# Load_Sig_Sch.net
KiCad netlist of a schematic drawn in EAGLE
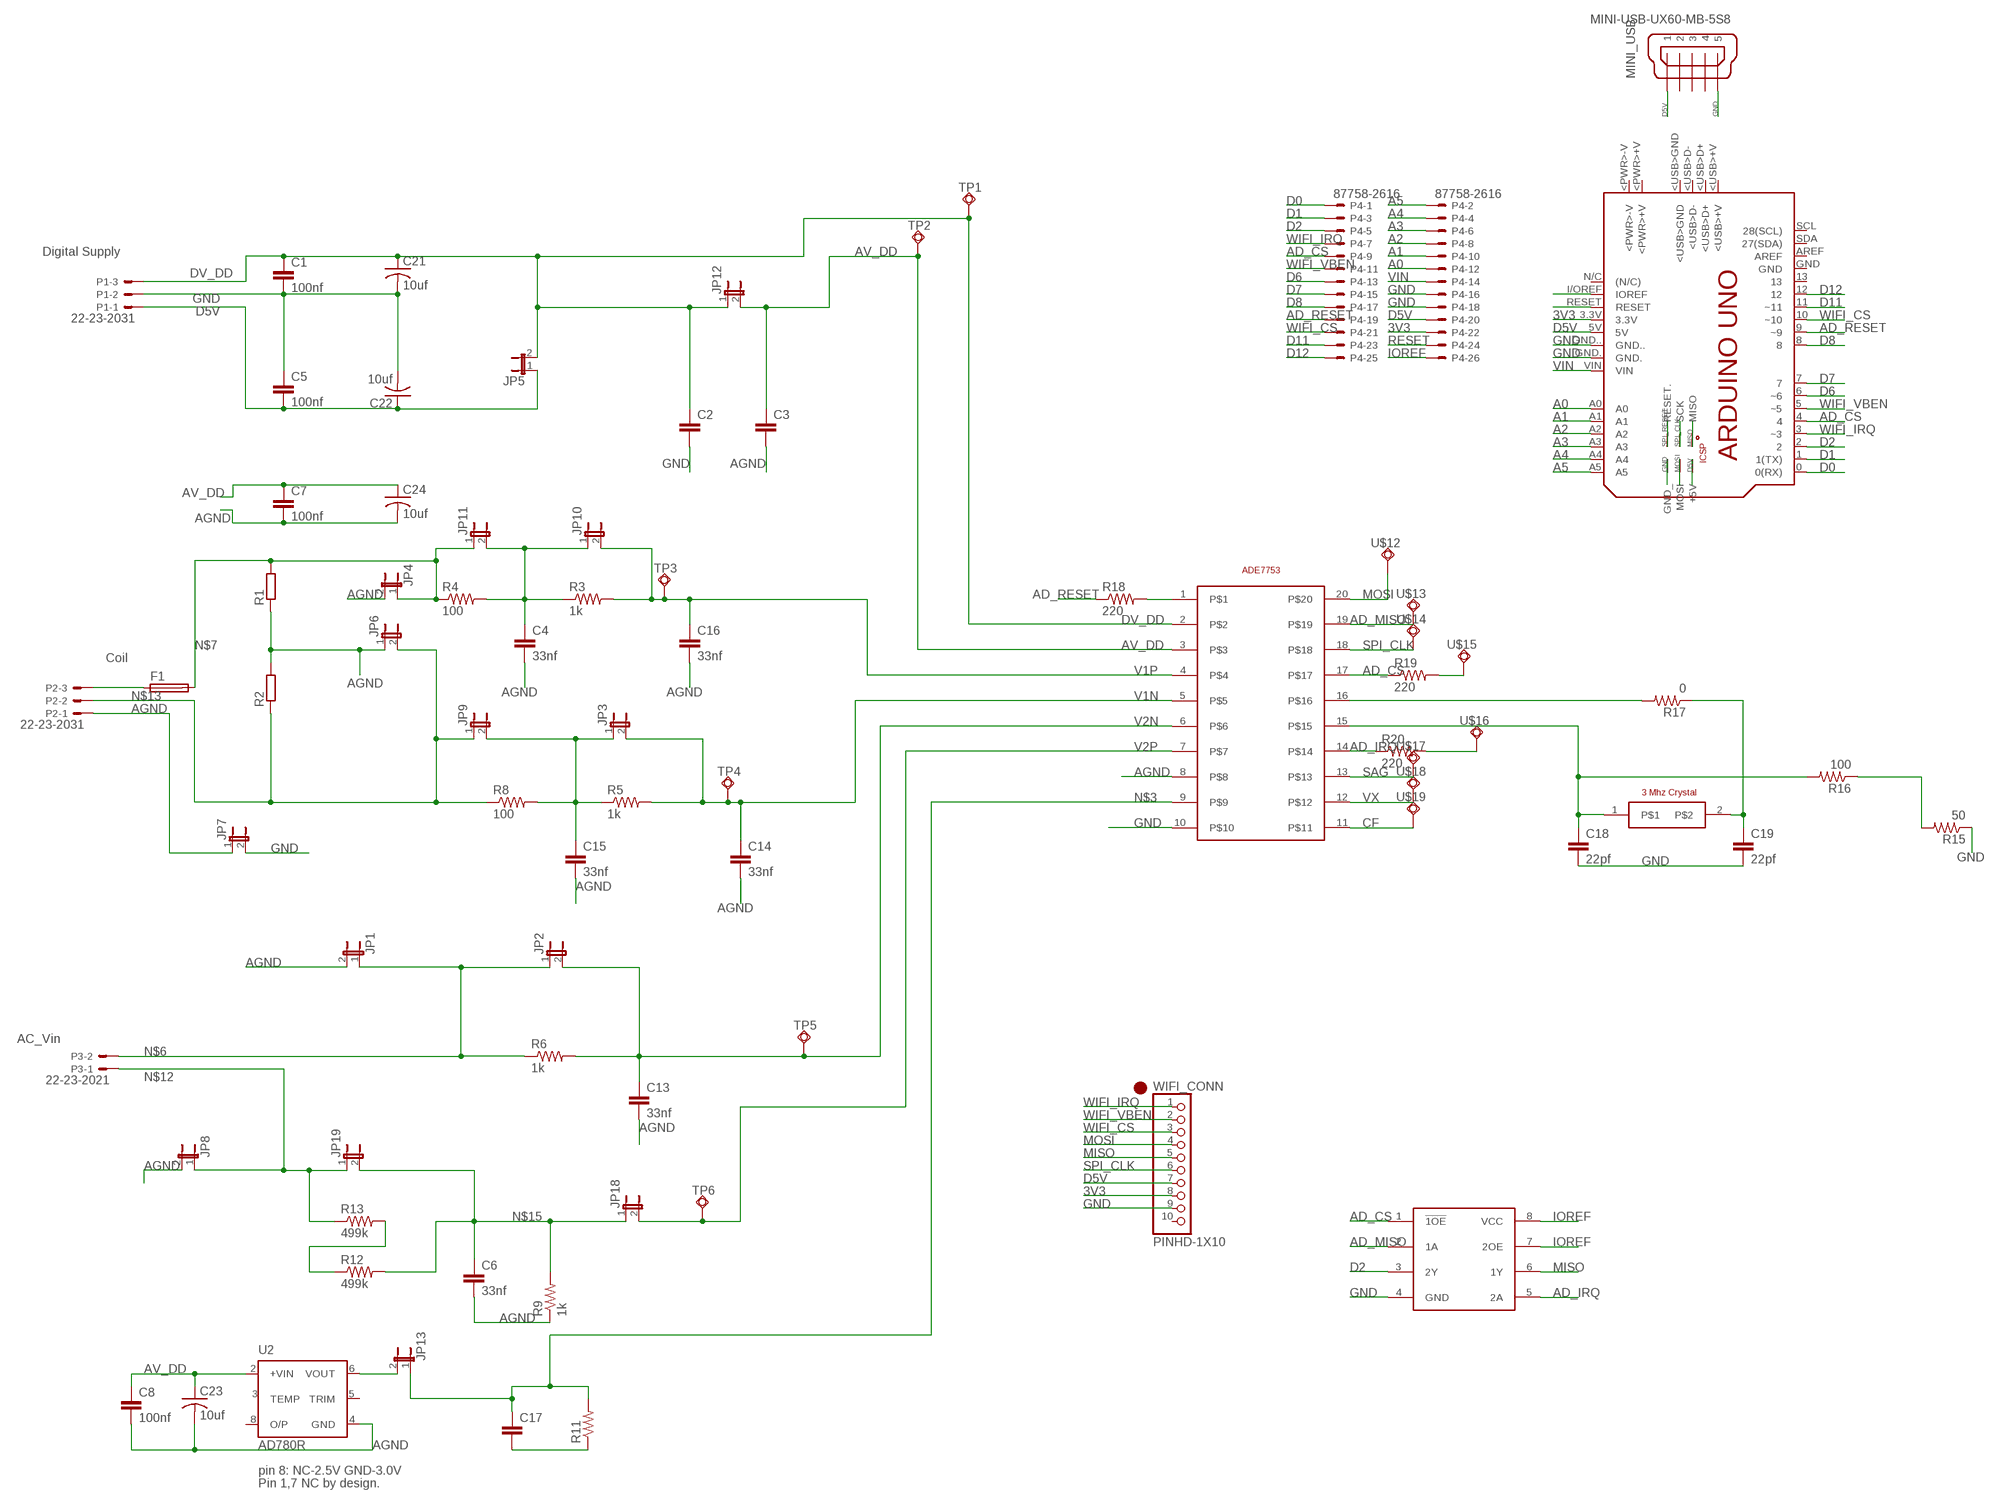
[diagram p0: schematic, sheet 1]

(export (version "E")
  (design (tool "Eeschema 10.0.6"))
  (components
    (comp (ref "C1")
      (value "100nf")
      (footprint "eagle-import:C025-024X044")
      (libsource (lib "eagle-import") (part "resistor_C-EU025-024X044"))
    )
    (comp (ref "C2")
      (value "C-EU025-024X044")
      (footprint "eagle-import:C025-024X044")
      (libsource (lib "eagle-import") (part "resistor_C-EU025-024X044"))
    )
    (comp (ref "C3")
      (value "C-EU025-024X044")
      (footprint "eagle-import:C025-024X044")
      (libsource (lib "eagle-import") (part "resistor_C-EU025-024X044"))
    )
    (comp (ref "C4")
      (value "33nf")
      (footprint "eagle-import:C025-024X044")
      (libsource (lib "eagle-import") (part "resistor_C-EU025-024X044"))
    )
    (comp (ref "C5")
      (value "100nf")
      (footprint "eagle-import:C025-024X044")
      (libsource (lib "eagle-import") (part "resistor_C-EU025-024X044"))
    )
    (comp (ref "C6")
      (value "33nf")
      (footprint "eagle-import:C025-024X044")
      (libsource (lib "eagle-import") (part "resistor_C-EU025-024X044"))
    )
    (comp (ref "C7")
      (value "100nf")
      (footprint "eagle-import:C025-024X044")
      (libsource (lib "eagle-import") (part "resistor_C-EU025-024X044"))
    )
    (comp (ref "C8")
      (value "100nf")
      (footprint "eagle-import:C025-024X044")
      (libsource (lib "eagle-import") (part "resistor_C-EU025-024X044"))
    )
    (comp (ref "C13")
      (value "33nf")
      (footprint "eagle-import:C025-024X044")
      (libsource (lib "eagle-import") (part "resistor_C-EU025-024X044"))
    )
    (comp (ref "C14")
      (value "33nf")
      (footprint "eagle-import:C025-024X044")
      (libsource (lib "eagle-import") (part "resistor_C-EU025-024X044"))
    )
    (comp (ref "C15")
      (value "33nf")
      (footprint "eagle-import:C025-024X044")
      (libsource (lib "eagle-import") (part "resistor_C-EU025-024X044"))
    )
    (comp (ref "C16")
      (value "33nf")
      (footprint "eagle-import:C025-024X044")
      (libsource (lib "eagle-import") (part "resistor_C-EU025-024X044"))
    )
    (comp (ref "C17")
      (value "C-EU025-024X044")
      (footprint "eagle-import:C025-024X044")
      (libsource (lib "eagle-import") (part "resistor_C-EU025-024X044"))
    )
    (comp (ref "C18")
      (value "22pf")
      (footprint "eagle-import:C025-024X044")
      (libsource (lib "eagle-import") (part "C-EU025-024X044"))
    )
    (comp (ref "C19")
      (value "22pf")
      (footprint "eagle-import:C025-024X044")
      (libsource (lib "eagle-import") (part "C-EU025-024X044"))
    )
    (comp (ref "C21")
      (value "10uf")
      (footprint "eagle-import:C025-024X044")
      (libsource (lib "eagle-import") (part "C-US025-024X044"))
    )
    (comp (ref "C22")
      (value "10uf")
      (footprint "eagle-import:C025-024X044")
      (libsource (lib "eagle-import") (part "C-US025-024X044"))
    )
    (comp (ref "C23")
      (value "10uf")
      (footprint "eagle-import:C025-024X044")
      (libsource (lib "eagle-import") (part "C-US025-024X044"))
    )
    (comp (ref "C24")
      (value "10uf")
      (footprint "eagle-import:C025-024X044")
      (libsource (lib "eagle-import") (part "C-US025-024X044"))
    )
    (comp (ref "F1")
      (value "19560")
      (footprint "eagle-import:19560")
      (fields (field (name "MPN") "56000001009"))
      (libsource (lib "eagle-import") (part "19560"))
    )
    (comp (ref "JP1")
      (value "JP1E")
      (footprint "eagle-import:JP1")
      (libsource (lib "eagle-import") (part "JP1E"))
    )
    (comp (ref "JP2")
      (value "JP1E")
      (footprint "eagle-import:JP1")
      (libsource (lib "eagle-import") (part "JP1E"))
    )
    (comp (ref "JP3")
      (value "JP1E")
      (footprint "eagle-import:JP1")
      (libsource (lib "eagle-import") (part "JP1E"))
    )
    (comp (ref "JP4")
      (value "JP1E")
      (footprint "eagle-import:JP1")
      (libsource (lib "eagle-import") (part "JP1E"))
    )
    (comp (ref "JP5")
      (value "JP1E")
      (footprint "eagle-import:JP1")
      (libsource (lib "eagle-import") (part "JP1E"))
    )
    (comp (ref "JP6")
      (value "JP1E")
      (footprint "eagle-import:JP1")
      (libsource (lib "eagle-import") (part "JP1E"))
    )
    (comp (ref "JP7")
      (value "JP1E")
      (footprint "eagle-import:JP1")
      (libsource (lib "eagle-import") (part "JP1E"))
    )
    (comp (ref "JP8")
      (value "JP1E")
      (footprint "eagle-import:JP1")
      (libsource (lib "eagle-import") (part "JP1E"))
    )
    (comp (ref "JP9")
      (value "JP1E")
      (footprint "eagle-import:JP1")
      (libsource (lib "eagle-import") (part "JP1E"))
    )
    (comp (ref "JP10")
      (value "JP1E")
      (footprint "eagle-import:JP1")
      (libsource (lib "eagle-import") (part "JP1E"))
    )
    (comp (ref "JP11")
      (value "JP1E")
      (footprint "eagle-import:JP1")
      (libsource (lib "eagle-import") (part "JP1E"))
    )
    (comp (ref "JP12")
      (value "JP1E")
      (footprint "eagle-import:JP1")
      (libsource (lib "eagle-import") (part "JP1E"))
    )
    (comp (ref "JP13")
      (value "JP1E")
      (footprint "eagle-import:JP1")
      (libsource (lib "eagle-import") (part "JP1E"))
    )
    (comp (ref "JP18")
      (value "JP1E")
      (footprint "eagle-import:JP1")
      (libsource (lib "eagle-import") (part "JP1E"))
    )
    (comp (ref "JP19")
      (value "JP1E")
      (footprint "eagle-import:JP1")
      (libsource (lib "eagle-import") (part "JP1E"))
    )
    (comp (ref "MINI_USB")
      (value "MINI-USB-UX60-MB-5S8")
      (footprint "eagle-import:UX60-MB-5S8")
      (libsource (lib "eagle-import") (part "MINI-USB-UX60-MB-5S8"))
    )
    (comp (ref "P1")
      (value "22-23-2031")
      (footprint "eagle-import:22-23-2031")
      (fields (field (name "MF") "MOLEX"))
      (libsource (lib "eagle-import") (part "22-23-2031"))
    )
    (comp (ref "P2")
      (value "22-23-2031")
      (footprint "eagle-import:22-23-2031")
      (fields (field (name "MF") "MOLEX"))
      (libsource (lib "eagle-import") (part "22-23-2031"))
    )
    (comp (ref "P3")
      (value "22-23-2021")
      (footprint "eagle-import:22-23-2021")
      (fields (field (name "MF") "MOLEX"))
      (libsource (lib "eagle-import") (part "22-23-2021"))
    )
    (comp (ref "P4")
      (value "87758-2616")
      (footprint "eagle-import:87758-2616")
      (libsource (lib "eagle-import") (part "87758-2616"))
    )
    (comp (ref "PCB1")
      (value "ARDUINO_UNO")
      (footprint "eagle-import:ARDUINO_UNO")
      (libsource (lib "eagle-import") (part "ARDUINO_UNO"))
    )
    (comp (ref "R1")
      (value "BVS")
      (footprint "eagle-import:BVS")
      (libsource (lib "eagle-import") (part "BVS"))
    )
    (comp (ref "R2")
      (value "BVS")
      (footprint "eagle-import:BVS")
      (libsource (lib "eagle-import") (part "BVS"))
    )
    (comp (ref "R3")
      (value "1k")
      (footprint "eagle-import:0204V")
      (libsource (lib "eagle-import") (part "R-US_0204/2V"))
    )
    (comp (ref "R4")
      (value "100")
      (footprint "eagle-import:0204V")
      (libsource (lib "eagle-import") (part "R-US_0204/2V"))
    )
    (comp (ref "R5")
      (value "1k")
      (footprint "eagle-import:0204V")
      (libsource (lib "eagle-import") (part "R-US_0204/2V"))
    )
    (comp (ref "R6")
      (value "1k")
      (footprint "eagle-import:0204V")
      (libsource (lib "eagle-import") (part "R-US_0204/2V"))
    )
    (comp (ref "R8")
      (value "100")
      (footprint "eagle-import:0204V")
      (libsource (lib "eagle-import") (part "R-US_0204/2V"))
    )
    (comp (ref "R9")
      (value "1k")
      (footprint "eagle-import:0204V")
      (libsource (lib "eagle-import") (part "R-US_0204/2V"))
    )
    (comp (ref "R11")
      (value "R-US_0204/2V")
      (footprint "eagle-import:0204V")
      (libsource (lib "eagle-import") (part "R-US_0204/2V"))
    )
    (comp (ref "R12")
      (value "499k")
      (footprint "eagle-import:0204V")
      (libsource (lib "eagle-import") (part "R-US_0204/2V"))
    )
    (comp (ref "R13")
      (value "499k")
      (footprint "eagle-import:0204V")
      (libsource (lib "eagle-import") (part "R-US_0204/2V"))
    )
    (comp (ref "R15")
      (value "50")
      (footprint "eagle-import:0204V")
      (libsource (lib "eagle-import") (part "R-US_0204/2V"))
    )
    (comp (ref "R16")
      (value "100")
      (footprint "eagle-import:0204V")
      (libsource (lib "eagle-import") (part "R-US_0204/2V"))
    )
    (comp (ref "R17")
      (value "0")
      (footprint "eagle-import:0204V")
      (libsource (lib "eagle-import") (part "R-US_0204/2V"))
    )
    (comp (ref "R18")
      (value "220")
      (footprint "eagle-import:0603-RES")
      (libsource (lib "eagle-import") (part "RESISTOR0603-RES"))
    )
    (comp (ref "R19")
      (value "220")
      (footprint "eagle-import:0603-RES")
      (libsource (lib "eagle-import") (part "RESISTOR0603-RES"))
    )
    (comp (ref "R20")
      (value "220")
      (footprint "eagle-import:0603-RES")
      (libsource (lib "eagle-import") (part "RESISTOR0603-RES"))
    )
    (comp (ref "TP1")
      (value "TEST")
      (footprint "eagle-import:TEST")
      (libsource (lib "eagle-import") (part "TEST"))
    )
    (comp (ref "TP2")
      (value "TEST")
      (footprint "eagle-import:TEST")
      (libsource (lib "eagle-import") (part "TEST"))
    )
    (comp (ref "TP3")
      (value "TEST")
      (footprint "eagle-import:TEST")
      (libsource (lib "eagle-import") (part "TEST"))
    )
    (comp (ref "TP4")
      (value "TEST")
      (footprint "eagle-import:TEST")
      (libsource (lib "eagle-import") (part "TEST"))
    )
    (comp (ref "TP5")
      (value "TEST")
      (footprint "eagle-import:TEST")
      (libsource (lib "eagle-import") (part "TEST"))
    )
    (comp (ref "TP6")
      (value "TEST")
      (footprint "eagle-import:TEST")
      (libsource (lib "eagle-import") (part "TEST"))
    )
    (comp (ref "U$2")
      (value "X079-ND_CRYSTAL")
      (footprint "eagle-import:HC49US")
      (libsource (lib "eagle-import") (part "X079-ND_CRYSTAL"))
    )
    (comp (ref "U$12")
      (value "TEST")
      (footprint "eagle-import:TEST")
      (libsource (lib "eagle-import") (part "TEST"))
    )
    (comp (ref "U$13")
      (value "TEST")
      (footprint "eagle-import:TEST")
      (libsource (lib "eagle-import") (part "TEST"))
    )
    (comp (ref "U$14")
      (value "TEST")
      (footprint "eagle-import:TEST")
      (libsource (lib "eagle-import") (part "TEST"))
    )
    (comp (ref "U$15")
      (value "TEST")
      (footprint "eagle-import:TEST")
      (libsource (lib "eagle-import") (part "TEST"))
    )
    (comp (ref "U$16")
      (value "TEST")
      (footprint "eagle-import:TEST")
      (libsource (lib "eagle-import") (part "TEST"))
    )
    (comp (ref "U$17")
      (value "TEST")
      (footprint "eagle-import:TEST")
      (libsource (lib "eagle-import") (part "TEST"))
    )
    (comp (ref "U$18")
      (value "TEST")
      (footprint "eagle-import:TEST")
      (libsource (lib "eagle-import") (part "TEST"))
    )
    (comp (ref "U$19")
      (value "TEST")
      (footprint "eagle-import:TEST")
      (libsource (lib "eagle-import") (part "TEST"))
    )
    (comp (ref "U1")
      (value "ADE7753")
      (footprint "eagle-import:SSOP20")
      (libsource (lib "eagle-import") (part "ADE7753"))
    )
    (comp (ref "U2")
      (value "AD780R")
      (footprint "eagle-import:SO8")
      (fields (field (name "MPN") "AD780BRZ-REEL"))
      (libsource (lib "eagle-import") (part "AD780R"))
    )
    (comp (ref "U3")
      (value "74LVC2G241")
      (footprint "eagle-import:SOP65P490X110-8N")
      (libsource (lib "eagle-import") (part "74LVC2G241"))
    )
    (comp (ref "WIFI_CONN")
      (value "PINHD-1X10")
      (footprint "eagle-import:1X10-BIG")
      (libsource (lib "eagle-import") (part "PINHD-1X10"))
    )
  )
  (nets
    (net (code "1") (name "/3V3") (class "Default")
      (node (ref "P4") (pin "22") (pinfunction "S_22") (pintype "passive"))
      (node (ref "PCB1") (pin "3.3V") (pinfunction "3.3V_3.3V") (pintype "bidirectional"))
      (node (ref "WIFI_CONN") (pin "8") (pinfunction "8_8") (pintype "passive"))
    )
    (net (code "2") (name "/A0") (class "Default")
      (node (ref "P4") (pin "12") (pinfunction "S_12") (pintype "passive"))
      (node (ref "PCB1") (pin "A0") (pinfunction "A0_A0") (pintype "bidirectional"))
    )
    (net (code "3") (name "/A1") (class "Default")
      (node (ref "P4") (pin "10") (pinfunction "S_10") (pintype "passive"))
      (node (ref "PCB1") (pin "A1") (pinfunction "A1_A1") (pintype "bidirectional"))
    )
    (net (code "4") (name "/A2") (class "Default")
      (node (ref "P4") (pin "8") (pinfunction "S_8") (pintype "passive"))
      (node (ref "PCB1") (pin "A2") (pinfunction "A2_A2") (pintype "bidirectional"))
    )
    (net (code "5") (name "/A3") (class "Default")
      (node (ref "P4") (pin "6") (pinfunction "S_6") (pintype "passive"))
      (node (ref "PCB1") (pin "A3") (pinfunction "A3_A3") (pintype "bidirectional"))
    )
    (net (code "6") (name "/A4") (class "Default")
      (node (ref "P4") (pin "4") (pinfunction "S_4") (pintype "passive"))
      (node (ref "PCB1") (pin "A4") (pinfunction "A4_A4") (pintype "bidirectional"))
    )
    (net (code "7") (name "/A5") (class "Default")
      (node (ref "P4") (pin "2") (pinfunction "S_2") (pintype "passive"))
      (node (ref "PCB1") (pin "A5") (pinfunction "A5_A5") (pintype "bidirectional"))
    )
    (net (code "8") (name "/AD_CS") (class "Default")
      (node (ref "P4") (pin "9") (pinfunction "S_9") (pintype "passive"))
      (node (ref "PCB1") (pin "4") (pinfunction "4_4") (pintype "bidirectional"))
      (node (ref "R19") (pin "1") (pinfunction "1_1") (pintype "passive"))
      (node (ref "U1") (pin "17") (pinfunction "P$17_17") (pintype "bidirectional"))
      (node (ref "U3") (pin "1") (pinfunction "~{1OE}_1") (pintype "bidirectional"))
    )
    (net (code "9") (name "/AD_IRQ") (class "Default")
      (node (ref "R20") (pin "1") (pinfunction "1_1") (pintype "passive"))
      (node (ref "U1") (pin "14") (pinfunction "P$14_14") (pintype "bidirectional"))
      (node (ref "U3") (pin "5") (pinfunction "2A_5") (pintype "bidirectional"))
    )
    (net (code "10") (name "/AD_MISO") (class "Default")
      (node (ref "U$13") (pin "1") (pinfunction "1_1") (pintype "input"))
      (node (ref "U1") (pin "19") (pinfunction "P$19_19") (pintype "bidirectional"))
      (node (ref "U3") (pin "2") (pinfunction "1A_2") (pintype "bidirectional"))
    )
    (net (code "11") (name "/AD_RESET") (class "Default")
      (node (ref "P4") (pin "19") (pinfunction "S_19") (pintype "passive"))
      (node (ref "PCB1") (pin "9") (pinfunction "~{9}_9") (pintype "bidirectional"))
      (node (ref "R18") (pin "1") (pinfunction "1_1") (pintype "passive"))
    )
    (net (code "12") (name "/AGND") (class "Default")
      (node (ref "C13") (pin "2") (pinfunction "2_2") (pintype "passive"))
      (node (ref "C14") (pin "2") (pinfunction "2_2") (pintype "passive"))
      (node (ref "C15") (pin "2") (pinfunction "2_2") (pintype "passive"))
      (node (ref "C16") (pin "2") (pinfunction "2_2") (pintype "passive"))
      (node (ref "C23") (pin "2") (pinfunction "2_2") (pintype "passive"))
      (node (ref "C24") (pin "2") (pinfunction "2_2") (pintype "passive"))
      (node (ref "C3") (pin "2") (pinfunction "2_2") (pintype "passive"))
      (node (ref "C4") (pin "2") (pinfunction "2_2") (pintype "passive"))
      (node (ref "C6") (pin "2") (pinfunction "2_2") (pintype "passive"))
      (node (ref "C7") (pin "2") (pinfunction "2_2") (pintype "passive"))
      (node (ref "C8") (pin "2") (pinfunction "2_2") (pintype "passive"))
      (node (ref "JP1") (pin "2") (pinfunction "2_2") (pintype "passive"))
      (node (ref "JP4") (pin "2") (pinfunction "2_2") (pintype "passive"))
      (node (ref "JP6") (pin "1") (pinfunction "1_1") (pintype "passive"))
      (node (ref "JP7") (pin "1") (pinfunction "1_1") (pintype "passive"))
      (node (ref "JP8") (pin "2") (pinfunction "2_2") (pintype "passive"))
      (node (ref "P2") (pin "1") (pinfunction "S_1") (pintype "passive"))
      (node (ref "R1") (pin "2") (pinfunction "2_2") (pintype "passive"))
      (node (ref "R2") (pin "1") (pinfunction "1_1") (pintype "passive"))
      (node (ref "R9") (pin "1") (pinfunction "1_1") (pintype "passive"))
      (node (ref "U1") (pin "8") (pinfunction "P$8_8") (pintype "bidirectional"))
      (node (ref "U2") (pin "4") (pinfunction "GND_4") (pintype "power_in"))
    )
    (net (code "13") (name "/AV_DD") (class "Default")
      (node (ref "C23") (pin "1") (pinfunction "1_1") (pintype "passive"))
      (node (ref "C24") (pin "1") (pinfunction "1_1") (pintype "passive"))
      (node (ref "C3") (pin "1") (pinfunction "1_1") (pintype "passive"))
      (node (ref "C7") (pin "1") (pinfunction "1_1") (pintype "passive"))
      (node (ref "C8") (pin "1") (pinfunction "1_1") (pintype "passive"))
      (node (ref "JP12") (pin "2") (pinfunction "2_2") (pintype "passive"))
      (node (ref "TP2") (pin "1") (pinfunction "1_1") (pintype "input"))
      (node (ref "U1") (pin "3") (pinfunction "P$3_3") (pintype "bidirectional"))
      (node (ref "U2") (pin "2") (pinfunction "+VIN_2") (pintype "input"))
    )
    (net (code "14") (name "/CF") (class "Default")
      (node (ref "U$19") (pin "1") (pinfunction "1_1") (pintype "input"))
      (node (ref "U1") (pin "11") (pinfunction "P$11_11") (pintype "bidirectional"))
    )
    (net (code "15") (name "/D0") (class "Default")
      (node (ref "P4") (pin "1") (pinfunction "S_1") (pintype "passive"))
      (node (ref "PCB1") (pin "0") (pinfunction "0(RX)_0") (pintype "bidirectional"))
    )
    (net (code "16") (name "/D1") (class "Default")
      (node (ref "P4") (pin "3") (pinfunction "S_3") (pintype "passive"))
      (node (ref "PCB1") (pin "1") (pinfunction "1(TX)_1") (pintype "bidirectional"))
    )
    (net (code "17") (name "/D2") (class "Default")
      (node (ref "P4") (pin "5") (pinfunction "S_5") (pintype "passive"))
      (node (ref "PCB1") (pin "2") (pinfunction "2_2") (pintype "bidirectional"))
      (node (ref "U3") (pin "3") (pinfunction "2Y_3") (pintype "bidirectional"))
    )
    (net (code "18") (name "/D5V") (class "Default")
      (node (ref "C22") (pin "1") (pinfunction "1_1") (pintype "passive"))
      (node (ref "C5") (pin "2") (pinfunction "2_2") (pintype "passive"))
      (node (ref "JP5") (pin "1") (pinfunction "1_1") (pintype "passive"))
      (node (ref "MINI_USB") (pin "1") (pinfunction "1_1") (pintype "input"))
      (node (ref "P1") (pin "1") (pinfunction "S_1") (pintype "passive"))
      (node (ref "P4") (pin "20") (pinfunction "S_20") (pintype "passive"))
      (node (ref "PCB1") (pin "+5V") (pinfunction "+5V_+5V") (pintype "bidirectional"))
      (node (ref "PCB1") (pin "5V") (pinfunction "5V_5V") (pintype "bidirectional"))
      (node (ref "WIFI_CONN") (pin "7") (pinfunction "7_7") (pintype "passive"))
    )
    (net (code "19") (name "/D6") (class "Default")
      (node (ref "P4") (pin "13") (pinfunction "S_13") (pintype "passive"))
      (node (ref "PCB1") (pin "6") (pinfunction "~{6}_6") (pintype "bidirectional"))
    )
    (net (code "20") (name "/D7") (class "Default")
      (node (ref "P4") (pin "15") (pinfunction "S_15") (pintype "passive"))
      (node (ref "PCB1") (pin "7") (pinfunction "7_7") (pintype "bidirectional"))
    )
    (net (code "21") (name "/D8") (class "Default")
      (node (ref "P4") (pin "17") (pinfunction "S_17") (pintype "passive"))
      (node (ref "PCB1") (pin "8") (pinfunction "8_8") (pintype "bidirectional"))
    )
    (net (code "22") (name "/D11") (class "Default")
      (node (ref "P4") (pin "23") (pinfunction "S_23") (pintype "passive"))
      (node (ref "PCB1") (pin "11") (pinfunction "~{11}_11") (pintype "bidirectional"))
    )
    (net (code "23") (name "/D12") (class "Default")
      (node (ref "P4") (pin "25") (pinfunction "S_25") (pintype "passive"))
      (node (ref "PCB1") (pin "12") (pinfunction "12_12") (pintype "bidirectional"))
    )
    (net (code "24") (name "/DV_DD") (class "Default")
      (node (ref "C1") (pin "1") (pinfunction "1_1") (pintype "passive"))
      (node (ref "C2") (pin "1") (pinfunction "1_1") (pintype "passive"))
      (node (ref "C21") (pin "1") (pinfunction "1_1") (pintype "passive"))
      (node (ref "JP12") (pin "1") (pinfunction "1_1") (pintype "passive"))
      (node (ref "JP5") (pin "2") (pinfunction "2_2") (pintype "passive"))
      (node (ref "P1") (pin "3") (pinfunction "S_3") (pintype "passive"))
      (node (ref "TP1") (pin "1") (pinfunction "1_1") (pintype "input"))
      (node (ref "U1") (pin "2") (pinfunction "P$2_2") (pintype "bidirectional"))
    )
    (net (code "25") (name "/GND") (class "Default")
      (node (ref "C1") (pin "2") (pinfunction "2_2") (pintype "passive"))
      (node (ref "C18") (pin "2") (pinfunction "2_2") (pintype "passive"))
      (node (ref "C19") (pin "2") (pinfunction "2_2") (pintype "passive"))
      (node (ref "C2") (pin "2") (pinfunction "2_2") (pintype "passive"))
      (node (ref "C21") (pin "2") (pinfunction "2_2") (pintype "passive"))
      (node (ref "C22") (pin "2") (pinfunction "2_2") (pintype "passive"))
      (node (ref "C5") (pin "1") (pinfunction "1_1") (pintype "passive"))
      (node (ref "JP7") (pin "2") (pinfunction "2_2") (pintype "passive"))
      (node (ref "MINI_USB") (pin "5") (pinfunction "5_5") (pintype "input"))
      (node (ref "P1") (pin "2") (pinfunction "S_2") (pintype "passive"))
      (node (ref "P4") (pin "16") (pinfunction "S_16") (pintype "passive"))
      (node (ref "P4") (pin "18") (pinfunction "S_18") (pintype "passive"))
      (node (ref "PCB1") (pin "GND.") (pinfunction "GND._GND.") (pintype "bidirectional"))
      (node (ref "PCB1") (pin "GND..") (pinfunction "GND.._GND..") (pintype "bidirectional"))
      (node (ref "PCB1") (pin "GND_") (pinfunction "GND__GND_") (pintype "bidirectional"))
      (node (ref "R15") (pin "1") (pinfunction "1_1") (pintype "passive"))
      (node (ref "U1") (pin "10") (pinfunction "P$10_10") (pintype "bidirectional"))
      (node (ref "U3") (pin "4") (pinfunction "GND_4") (pintype "bidirectional"))
      (node (ref "WIFI_CONN") (pin "9") (pinfunction "9_9") (pintype "passive"))
    )
    (net (code "26") (name "/IOREF") (class "Default")
      (node (ref "P4") (pin "26") (pinfunction "S_26") (pintype "passive"))
      (node (ref "PCB1") (pin "I/OREF") (pinfunction "IOREF_I/OREF") (pintype "bidirectional"))
      (node (ref "U3") (pin "7") (pinfunction "2OE_7") (pintype "bidirectional"))
      (node (ref "U3") (pin "8") (pinfunction "VCC_8") (pintype "bidirectional"))
    )
    (net (code "27") (name "/MISO") (class "Default")
      (node (ref "PCB1") (pin "MISO") (pinfunction "MISO_MISO") (pintype "bidirectional"))
      (node (ref "U3") (pin "6") (pinfunction "1Y_6") (pintype "bidirectional"))
      (node (ref "WIFI_CONN") (pin "5") (pinfunction "5_5") (pintype "passive"))
    )
    (net (code "28") (name "/MOSI") (class "Default")
      (node (ref "PCB1") (pin "MOSI") (pinfunction "MOSI_MOSI") (pintype "bidirectional"))
      (node (ref "U$12") (pin "1") (pinfunction "1_1") (pintype "input"))
      (node (ref "U1") (pin "20") (pinfunction "P$20_20") (pintype "bidirectional"))
      (node (ref "WIFI_CONN") (pin "4") (pinfunction "4_4") (pintype "passive"))
    )
    (net (code "29") (name "/N$3") (class "Default")
      (node (ref "C17") (pin "1") (pinfunction "1_1") (pintype "passive"))
      (node (ref "JP13") (pin "1") (pinfunction "1_1") (pintype "passive"))
      (node (ref "R11") (pin "2") (pinfunction "2_2") (pintype "passive"))
      (node (ref "U1") (pin "9") (pinfunction "P$9_9") (pintype "bidirectional"))
    )
    (net (code "30") (name "/N$6") (class "Default")
      (node (ref "JP1") (pin "1") (pinfunction "1_1") (pintype "passive"))
      (node (ref "JP2") (pin "1") (pinfunction "1_1") (pintype "passive"))
      (node (ref "P3") (pin "2") (pinfunction "S_2") (pintype "passive"))
      (node (ref "R6") (pin "1") (pinfunction "1_1") (pintype "passive"))
    )
    (net (code "31") (name "/N$7") (class "Default")
      (node (ref "F1") (pin "2") (pinfunction "2_2") (pintype "passive"))
      (node (ref "JP11") (pin "1") (pinfunction "1_1") (pintype "passive"))
      (node (ref "JP4") (pin "1") (pinfunction "1_1") (pintype "passive"))
      (node (ref "R1") (pin "1") (pinfunction "1_1") (pintype "passive"))
      (node (ref "R4") (pin "1") (pinfunction "1_1") (pintype "passive"))
    )
    (net (code "32") (name "/N$12") (class "Default")
      (node (ref "JP19") (pin "1") (pinfunction "1_1") (pintype "passive"))
      (node (ref "JP8") (pin "1") (pinfunction "1_1") (pintype "passive"))
      (node (ref "P3") (pin "1") (pinfunction "S_1") (pintype "passive"))
      (node (ref "R13") (pin "1") (pinfunction "1_1") (pintype "passive"))
    )
    (net (code "33") (name "/N$13") (class "Default")
      (node (ref "JP6") (pin "2") (pinfunction "2_2") (pintype "passive"))
      (node (ref "JP9") (pin "1") (pinfunction "1_1") (pintype "passive"))
      (node (ref "P2") (pin "2") (pinfunction "S_2") (pintype "passive"))
      (node (ref "R2") (pin "2") (pinfunction "2_2") (pintype "passive"))
      (node (ref "R8") (pin "1") (pinfunction "1_1") (pintype "passive"))
    )
    (net (code "34") (name "/N$15") (class "Default")
      (node (ref "C6") (pin "1") (pinfunction "1_1") (pintype "passive"))
      (node (ref "JP18") (pin "1") (pinfunction "1_1") (pintype "passive"))
      (node (ref "JP19") (pin "2") (pinfunction "2_2") (pintype "passive"))
      (node (ref "R12") (pin "2") (pinfunction "2_2") (pintype "passive"))
      (node (ref "R9") (pin "2") (pinfunction "2_2") (pintype "passive"))
    )
    (net (code "35") (name "/RESET") (class "Default")
      (node (ref "P4") (pin "24") (pinfunction "S_24") (pintype "passive"))
      (node (ref "PCB1") (pin "RESET") (pinfunction "RESET_RESET") (pintype "bidirectional"))
    )
    (net (code "36") (name "/SAG") (class "Default")
      (node (ref "U$17") (pin "1") (pinfunction "1_1") (pintype "input"))
      (node (ref "U1") (pin "13") (pinfunction "P$13_13") (pintype "bidirectional"))
    )
    (net (code "37") (name "/SPI_CLK") (class "Default")
      (node (ref "PCB1") (pin "SCK") (pinfunction "SCK_SCK") (pintype "bidirectional"))
      (node (ref "U$14") (pin "1") (pinfunction "1_1") (pintype "input"))
      (node (ref "U1") (pin "18") (pinfunction "P$18_18") (pintype "bidirectional"))
      (node (ref "WIFI_CONN") (pin "6") (pinfunction "6_6") (pintype "passive"))
    )
    (net (code "38") (name "/SPI_RESET") (class "Default")
      (node (ref "PCB1") (pin "RESET.") (pinfunction "RESET._RESET.") (pintype "bidirectional"))
    )
    (net (code "39") (name "/V1N") (class "Default")
      (node (ref "C14") (pin "1") (pinfunction "1_1") (pintype "passive"))
      (node (ref "JP3") (pin "2") (pinfunction "2_2") (pintype "passive"))
      (node (ref "R5") (pin "2") (pinfunction "2_2") (pintype "passive"))
      (node (ref "TP4") (pin "1") (pinfunction "1_1") (pintype "input"))
      (node (ref "U1") (pin "5") (pinfunction "P$5_5") (pintype "bidirectional"))
    )
    (net (code "40") (name "/V1P") (class "Default")
      (node (ref "C16") (pin "1") (pinfunction "1_1") (pintype "passive"))
      (node (ref "JP10") (pin "2") (pinfunction "2_2") (pintype "passive"))
      (node (ref "R3") (pin "2") (pinfunction "2_2") (pintype "passive"))
      (node (ref "TP3") (pin "1") (pinfunction "1_1") (pintype "input"))
      (node (ref "U1") (pin "4") (pinfunction "P$4_4") (pintype "bidirectional"))
    )
    (net (code "41") (name "/V2N") (class "Default")
      (node (ref "C13") (pin "1") (pinfunction "1_1") (pintype "passive"))
      (node (ref "JP2") (pin "2") (pinfunction "2_2") (pintype "passive"))
      (node (ref "R6") (pin "2") (pinfunction "2_2") (pintype "passive"))
      (node (ref "TP5") (pin "1") (pinfunction "1_1") (pintype "input"))
      (node (ref "U1") (pin "6") (pinfunction "P$6_6") (pintype "bidirectional"))
    )
    (net (code "42") (name "/V2P") (class "Default")
      (node (ref "JP18") (pin "2") (pinfunction "2_2") (pintype "passive"))
      (node (ref "TP6") (pin "1") (pinfunction "1_1") (pintype "input"))
      (node (ref "U1") (pin "7") (pinfunction "P$7_7") (pintype "bidirectional"))
    )
    (net (code "43") (name "/VIN") (class "Default")
      (node (ref "P4") (pin "14") (pinfunction "S_14") (pintype "passive"))
      (node (ref "PCB1") (pin "VIN") (pinfunction "VIN_VIN") (pintype "bidirectional"))
    )
    (net (code "44") (name "/VX") (class "Default")
      (node (ref "U$18") (pin "1") (pinfunction "1_1") (pintype "input"))
      (node (ref "U1") (pin "12") (pinfunction "P$12_12") (pintype "bidirectional"))
    )
    (net (code "45") (name "/WIFI_CS") (class "Default")
      (node (ref "P4") (pin "21") (pinfunction "S_21") (pintype "passive"))
      (node (ref "PCB1") (pin "10") (pinfunction "~{10}_10") (pintype "bidirectional"))
      (node (ref "WIFI_CONN") (pin "3") (pinfunction "3_3") (pintype "passive"))
    )
    (net (code "46") (name "/WIFI_IRQ") (class "Default")
      (node (ref "P4") (pin "7") (pinfunction "S_7") (pintype "passive"))
      (node (ref "PCB1") (pin "3") (pinfunction "~{3}_3") (pintype "bidirectional"))
      (node (ref "WIFI_CONN") (pin "1") (pinfunction "1_1") (pintype "passive"))
    )
    (net (code "47") (name "/WIFI_VBEN") (class "Default")
      (node (ref "P4") (pin "11") (pinfunction "S_11") (pintype "passive"))
      (node (ref "PCB1") (pin "5") (pinfunction "~{5}_5") (pintype "bidirectional"))
      (node (ref "WIFI_CONN") (pin "2") (pinfunction "2_2") (pintype "passive"))
    )
    (net (code "48") (name "Net-(C4-Pad1)") (class "Default")
      (node (ref "C4") (pin "1") (pinfunction "1_1") (pintype "passive"))
      (node (ref "JP10") (pin "1") (pinfunction "1_1") (pintype "passive"))
      (node (ref "JP11") (pin "2") (pinfunction "2_2") (pintype "passive"))
      (node (ref "R3") (pin "1") (pinfunction "1_1") (pintype "passive"))
      (node (ref "R4") (pin "2") (pinfunction "2_2") (pintype "passive"))
    )
    (net (code "49") (name "Net-(C15-Pad1)") (class "Default")
      (node (ref "C15") (pin "1") (pinfunction "1_1") (pintype "passive"))
      (node (ref "JP3") (pin "1") (pinfunction "1_1") (pintype "passive"))
      (node (ref "JP9") (pin "2") (pinfunction "2_2") (pintype "passive"))
      (node (ref "R5") (pin "1") (pinfunction "1_1") (pintype "passive"))
      (node (ref "R8") (pin "2") (pinfunction "2_2") (pintype "passive"))
    )
    (net (code "50") (name "Net-(C17-Pad2)") (class "Default")
      (node (ref "C17") (pin "2") (pinfunction "2_2") (pintype "passive"))
      (node (ref "R11") (pin "1") (pinfunction "1_1") (pintype "passive"))
    )
    (net (code "51") (name "Net-(P2C-S)") (class "Default")
      (node (ref "F1") (pin "1") (pinfunction "1_1") (pintype "passive"))
      (node (ref "P2") (pin "3") (pinfunction "S_3") (pintype "passive"))
    )
    (net (code "52") (name "Net-(R12-Pad1)") (class "Default")
      (node (ref "R12") (pin "1") (pinfunction "1_1") (pintype "passive"))
      (node (ref "R13") (pin "2") (pinfunction "2_2") (pintype "passive"))
    )
    (net (code "53") (name "Net-(R15-Pad2)") (class "Default")
      (node (ref "R15") (pin "2") (pinfunction "2_2") (pintype "passive"))
      (node (ref "R16") (pin "1") (pinfunction "1_1") (pintype "passive"))
    )
    (net (code "54") (name "Net-(R19-Pad2)") (class "Default")
      (node (ref "R19") (pin "2") (pinfunction "2_2") (pintype "passive"))
      (node (ref "U$15") (pin "1") (pinfunction "1_1") (pintype "input"))
    )
    (net (code "55") (name "Net-(R20-Pad2)") (class "Default")
      (node (ref "R20") (pin "2") (pinfunction "2_2") (pintype "passive"))
      (node (ref "U$16") (pin "1") (pinfunction "1_1") (pintype "input"))
    )
    (net (code "56") (name "Net-(U$2-P$1)") (class "Default")
      (node (ref "C18") (pin "1") (pinfunction "1_1") (pintype "passive"))
      (node (ref "R16") (pin "2") (pinfunction "2_2") (pintype "passive"))
      (node (ref "U$2") (pin "1") (pinfunction "P$1_1") (pintype "bidirectional"))
      (node (ref "U1") (pin "15") (pinfunction "P$15_15") (pintype "bidirectional"))
    )
    (net (code "57") (name "Net-(U$2-P$2)") (class "Default")
      (node (ref "C19") (pin "1") (pinfunction "1_1") (pintype "passive"))
      (node (ref "R17") (pin "1") (pinfunction "1_1") (pintype "passive"))
      (node (ref "U$2") (pin "2") (pinfunction "P$2_2") (pintype "bidirectional"))
    )
    (net (code "58") (name "Net-(U1-P$1)") (class "Default")
      (node (ref "R18") (pin "2") (pinfunction "2_2") (pintype "passive"))
      (node (ref "U1") (pin "1") (pinfunction "P$1_1") (pintype "bidirectional"))
    )
    (net (code "59") (name "Net-(U1-P$16)") (class "Default")
      (node (ref "R17") (pin "2") (pinfunction "2_2") (pintype "passive"))
      (node (ref "U1") (pin "16") (pinfunction "P$16_16") (pintype "bidirectional"))
    )
    (net (code "60") (name "Net-(U2-VOUT)") (class "Default")
      (node (ref "JP13") (pin "2") (pinfunction "2_2") (pintype "passive"))
      (node (ref "U2") (pin "6") (pinfunction "VOUT_6") (pintype "input"))
    )
    (net (code "61") (name "unconnected-(MINI_USB-Pad2)") (class "Default")
      (node (ref "MINI_USB") (pin "2") (pinfunction "2_2") (pintype "input"))
    )
    (net (code "62") (name "unconnected-(MINI_USB-Pad3)") (class "Default")
      (node (ref "MINI_USB") (pin "3") (pinfunction "3_3") (pintype "input"))
    )
    (net (code "63") (name "unconnected-(MINI_USB-Pad4)") (class "Default")
      (node (ref "MINI_USB") (pin "4") (pinfunction "4_4") (pintype "input"))
    )
    (net (code "64") (name "unconnected-(PCB1-(N{slash}C)-PadN{slash}C)") (class "Default")
      (node (ref "PCB1") (pin "N/C") (pinfunction "(N/C)_N/C") (pintype "bidirectional"))
    )
    (net (code "65") (name "unconnected-(PCB1-27(SDA)-PadSDA)") (class "Default")
      (node (ref "PCB1") (pin "SDA") (pinfunction "27(SDA)_SDA") (pintype "bidirectional"))
    )
    (net (code "66") (name "unconnected-(PCB1-28(SCL)-PadSCL)") (class "Default")
      (node (ref "PCB1") (pin "SCL") (pinfunction "28(SCL)_SCL") (pintype "bidirectional"))
    )
    (net (code "67") (name "unconnected-(PCB1-Pad13)") (class "Default")
      (node (ref "PCB1") (pin "13") (pinfunction "13_13") (pintype "bidirectional"))
    )
    (net (code "68") (name "unconnected-(PCB1-Pad<PWR>+V)") (class "Default")
      (node (ref "PCB1") (pin "<PWR>+V") (pinfunction "<PWR>+V_<PWR>+V") (pintype "bidirectional"))
    )
    (net (code "69") (name "unconnected-(PCB1-Pad<PWR>-V)") (class "Default")
      (node (ref "PCB1") (pin "<PWR>-V") (pinfunction "<PWR>-V_<PWR>-V") (pintype "bidirectional"))
    )
    (net (code "70") (name "unconnected-(PCB1-Pad<USB>+V)") (class "Default")
      (node (ref "PCB1") (pin "<USB>+V") (pinfunction "<USB>+V_<USB>+V") (pintype "bidirectional"))
    )
    (net (code "71") (name "unconnected-(PCB1-Pad<USB>D+)") (class "Default")
      (node (ref "PCB1") (pin "<USB>D+") (pinfunction "<USB>D+_<USB>D+") (pintype "bidirectional"))
    )
    (net (code "72") (name "unconnected-(PCB1-Pad<USB>D-)") (class "Default")
      (node (ref "PCB1") (pin "<USB>D-") (pinfunction "<USB>D-_<USB>D-") (pintype "bidirectional"))
    )
    (net (code "73") (name "unconnected-(PCB1-Pad<USB>GND)") (class "Default")
      (node (ref "PCB1") (pin "<USB>GND") (pinfunction "<USB>GND_<USB>GND") (pintype "bidirectional"))
    )
    (net (code "74") (name "unconnected-(PCB1-PadAREF)") (class "Default")
      (node (ref "PCB1") (pin "AREF") (pinfunction "AREF_AREF") (pintype "bidirectional"))
    )
    (net (code "75") (name "unconnected-(PCB1-PadGND)") (class "Default")
      (node (ref "PCB1") (pin "GND") (pinfunction "GND_GND") (pintype "bidirectional"))
    )
    (net (code "76") (name "unconnected-(U2-O{slash}P-Pad8)") (class "Default")
      (node (ref "U2") (pin "8") (pinfunction "O/P_8") (pintype "passive"))
    )
    (net (code "77") (name "unconnected-(U2-TEMP-Pad3)") (class "Default")
      (node (ref "U2") (pin "3") (pinfunction "TEMP_3") (pintype "input"))
    )
    (net (code "78") (name "unconnected-(U2-TRIM-Pad5)") (class "Default")
      (node (ref "U2") (pin "5") (pinfunction "TRIM_5") (pintype "input"))
    )
    (net (code "79") (name "unconnected-(WIFI_CONN-Pad10)") (class "Default")
      (node (ref "WIFI_CONN") (pin "10") (pinfunction "10_10") (pintype "passive"))
    )
  )
)
